# EnsembleSix.net
KiCad netlist of a schematic drawn in EAGLE
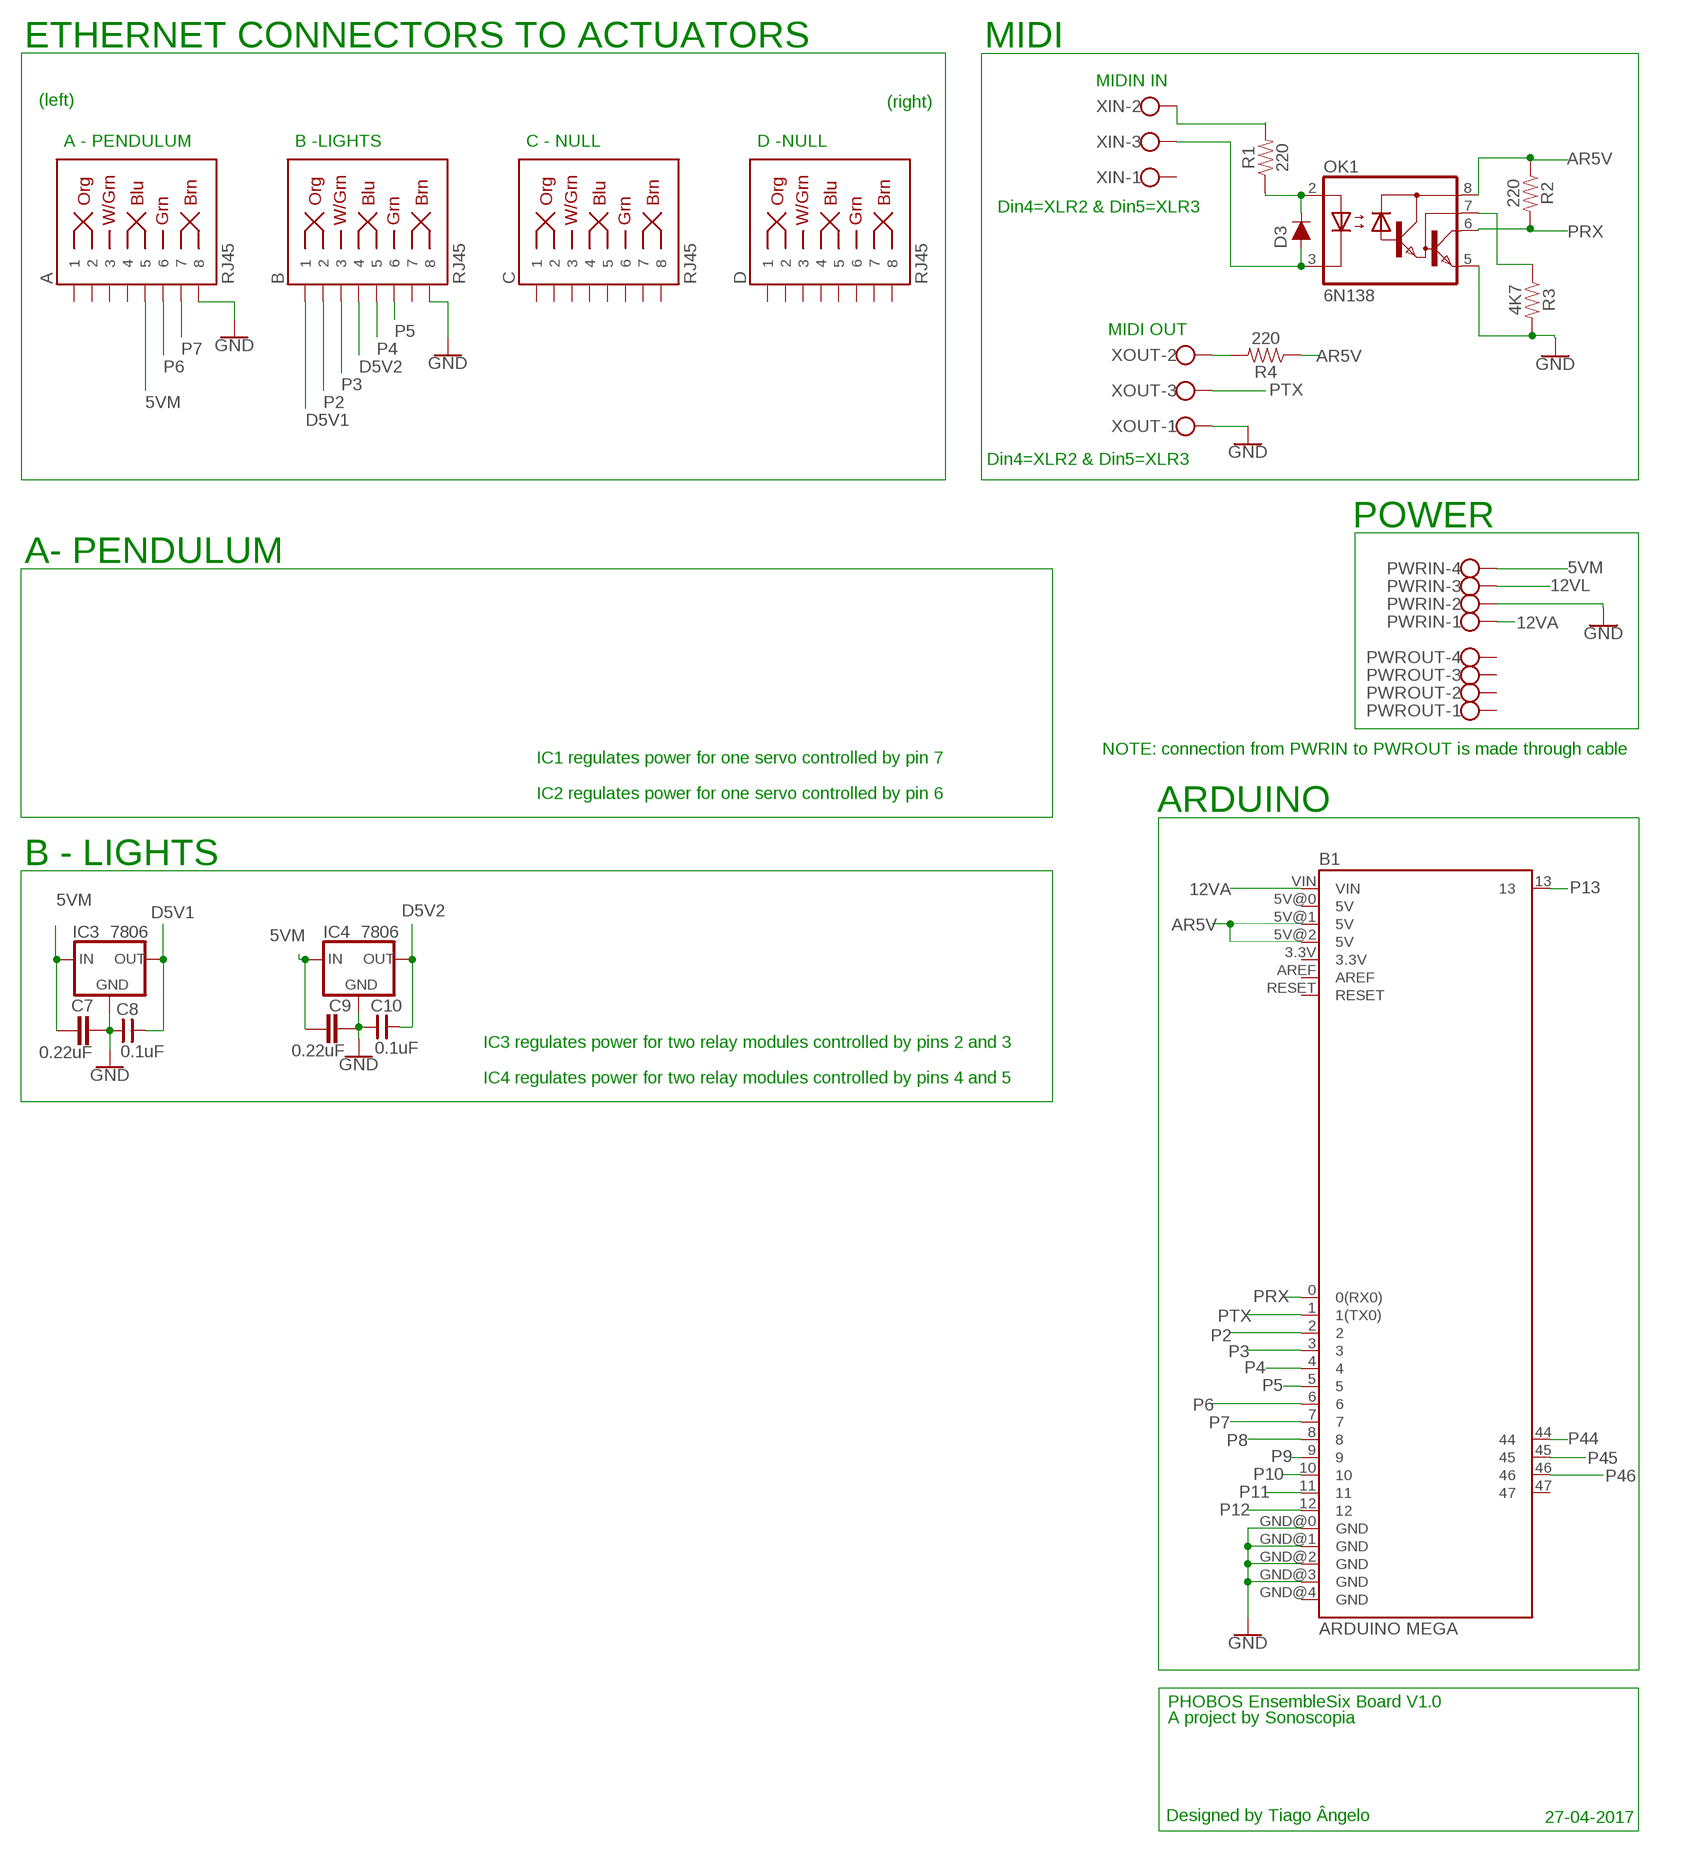
[diagram p0: schematic, sheet 1]

(export (version "E")
  (design (tool "Eeschema 10.0.6"))
  (components
    (comp (ref "A")
      (value "RJ45")
      (footprint "eagle-import:RJ45-8")
      (libsource (lib "eagle-import") (part "RJ45-8"))
    )
    (comp (ref "B")
      (value "RJ45")
      (footprint "eagle-import:RJ45-8")
      (libsource (lib "eagle-import") (part "RJ45-8"))
    )
    (comp (ref "B1")
      (value "ARDUINO MEGA")
      (footprint "eagle-import:ARDUINO_MEGA")
      (libsource (lib "eagle-import") (part "ARDUINO_MEGA_R3FULL"))
    )
    (comp (ref "C")
      (value "RJ45")
      (footprint "eagle-import:RJ45-8")
      (libsource (lib "eagle-import") (part "RJ45-8"))
    )
    (comp (ref "C7")
      (value "0.22uF")
      (footprint "eagle-import:C5B3")
      (libsource (lib "eagle-import") (part "C5/3"))
    )
    (comp (ref "C8")
      (value "0.1uF")
      (footprint "eagle-import:C025-050X025")
      (libsource (lib "eagle-import") (part "CNP-C025-050X025"))
    )
    (comp (ref "C9")
      (value "0.22uF")
      (footprint "eagle-import:C5B3")
      (libsource (lib "eagle-import") (part "C5/3"))
    )
    (comp (ref "C10")
      (value "0.1uF")
      (footprint "eagle-import:C025-050X025")
      (libsource (lib "eagle-import") (part "CNP-C025-050X025"))
    )
    (comp (ref "D")
      (value "RJ45")
      (footprint "eagle-import:RJ45-8")
      (libsource (lib "eagle-import") (part "RJ45-8"))
    )
    (comp (ref "D3")
      (value "200mA/100V/1V")
      (footprint "eagle-import:DIODE-1N4148")
      (libsource (lib "eagle-import") (part "DIODE-1N4148"))
    )
    (comp (ref "IC3")
      (value "7806")
      (footprint "eagle-import:78XXS")
      (libsource (lib "eagle-import") (part "78XXS"))
    )
    (comp (ref "IC4")
      (value "7806")
      (footprint "eagle-import:78XXS")
      (libsource (lib "eagle-import") (part "78XXS"))
    )
    (comp (ref "OK1")
      (value "6N138")
      (footprint "eagle-import:DIL08")
      (fields (field (name "MF") "VISHAY/TELEFUNKEN"))
      (libsource (lib "eagle-import") (part "6N138"))
    )
    (comp (ref "PWRIN")
      (value "W237-4")
      (footprint "eagle-import:W237-4")
      (libsource (lib "eagle-import") (part "W237-4"))
    )
    (comp (ref "PWROUT")
      (value "W237-4")
      (footprint "eagle-import:W237-4")
      (libsource (lib "eagle-import") (part "W237-4"))
    )
    (comp (ref "R1")
      (value "220")
      (footprint "eagle-import:AXIAL-0.3")
      (libsource (lib "eagle-import") (part "1KOHM-HORIZ-1/4W-5%"))
    )
    (comp (ref "R2")
      (value "220")
      (footprint "eagle-import:AXIAL-0.3")
      (libsource (lib "eagle-import") (part "1KOHM-HORIZ-1/4W-5%"))
    )
    (comp (ref "R3")
      (value "4K7")
      (footprint "eagle-import:AXIAL-0.3")
      (libsource (lib "eagle-import") (part "1KOHM-HORIZ-1/4W-5%"))
    )
    (comp (ref "R4")
      (value "220")
      (footprint "eagle-import:AXIAL-0.3")
      (libsource (lib "eagle-import") (part "1KOHM-HORIZ-1/4W-5%"))
    )
    (comp (ref "XIN")
      (value "W237-103")
      (footprint "eagle-import:W237-103")
      (fields (field (name "MPN") "237-103"))
      (libsource (lib "eagle-import") (part "W237-103"))
    )
    (comp (ref "XOUT")
      (value "W237-103")
      (footprint "eagle-import:W237-103")
      (fields (field (name "MPN") "237-103"))
      (libsource (lib "eagle-import") (part "W237-103"))
    )
  )
  (nets
    (net (code "1") (name "/5VM") (class "Default")
      (node (ref "A") (pin "5") (pinfunction "5_5") (pintype "bidirectional"))
      (node (ref "C7") (pin "1") (pinfunction "1_1") (pintype "passive"))
      (node (ref "C9") (pin "1") (pinfunction "1_1") (pintype "passive"))
      (node (ref "IC3") (pin "IN") (pinfunction "IN_IN") (pintype "input"))
      (node (ref "IC4") (pin "IN") (pinfunction "IN_IN") (pintype "input"))
      (node (ref "PWRIN") (pin "4") (pinfunction "KL_4") (pintype "passive"))
    )
    (net (code "2") (name "/12VA") (class "Default")
      (node (ref "B1") (pin "VIN") (pinfunction "VIN_VIN") (pintype "bidirectional"))
      (node (ref "PWRIN") (pin "1") (pinfunction "KL_1") (pintype "passive"))
    )
    (net (code "3") (name "/12VL") (class "Default")
      (node (ref "PWRIN") (pin "3") (pinfunction "KL_3") (pintype "passive"))
    )
    (net (code "4") (name "/AR5V") (class "Default")
      (node (ref "B1") (pin "5V@1") (pinfunction "5V_5V@1") (pintype "bidirectional"))
      (node (ref "B1") (pin "5V@2") (pinfunction "5V_5V@2") (pintype "bidirectional"))
      (node (ref "OK1") (pin "8") (pinfunction "VCC_8") (pintype "passive"))
      (node (ref "R2") (pin "P$1") (pinfunction "1_P$1") (pintype "passive"))
      (node (ref "R4") (pin "P$1") (pinfunction "1_P$1") (pintype "passive"))
    )
    (net (code "5") (name "/D5V1") (class "Default")
      (node (ref "B") (pin "1") (pinfunction "1_1") (pintype "bidirectional"))
      (node (ref "C8") (pin "2") (pinfunction "2_2") (pintype "passive"))
      (node (ref "IC3") (pin "OUT") (pinfunction "OUT_OUT") (pintype "passive"))
    )
    (net (code "6") (name "/D5V2") (class "Default")
      (node (ref "B") (pin "4") (pinfunction "4_4") (pintype "bidirectional"))
      (node (ref "C10") (pin "2") (pinfunction "2_2") (pintype "passive"))
      (node (ref "IC4") (pin "OUT") (pinfunction "OUT_OUT") (pintype "passive"))
    )
    (net (code "7") (name "/P2") (class "Default")
      (node (ref "B") (pin "2") (pinfunction "2_2") (pintype "bidirectional"))
      (node (ref "B1") (pin "2") (pinfunction "2_2") (pintype "bidirectional"))
    )
    (net (code "8") (name "/P3") (class "Default")
      (node (ref "B") (pin "3") (pinfunction "3_3") (pintype "bidirectional"))
      (node (ref "B1") (pin "3") (pinfunction "3_3") (pintype "bidirectional"))
    )
    (net (code "9") (name "/P4") (class "Default")
      (node (ref "B") (pin "5") (pinfunction "5_5") (pintype "bidirectional"))
      (node (ref "B1") (pin "4") (pinfunction "4_4") (pintype "bidirectional"))
    )
    (net (code "10") (name "/P5") (class "Default")
      (node (ref "B") (pin "6") (pinfunction "6_6") (pintype "bidirectional"))
      (node (ref "B1") (pin "5") (pinfunction "5_5") (pintype "bidirectional"))
    )
    (net (code "11") (name "/P6") (class "Default")
      (node (ref "A") (pin "6") (pinfunction "6_6") (pintype "bidirectional"))
      (node (ref "B1") (pin "6") (pinfunction "6_6") (pintype "bidirectional"))
    )
    (net (code "12") (name "/P7") (class "Default")
      (node (ref "A") (pin "7") (pinfunction "7_7") (pintype "bidirectional"))
      (node (ref "B1") (pin "7") (pinfunction "7_7") (pintype "bidirectional"))
    )
    (net (code "13") (name "/P8") (class "Default")
      (node (ref "B1") (pin "8") (pinfunction "8_8") (pintype "bidirectional"))
    )
    (net (code "14") (name "/P9") (class "Default")
      (node (ref "B1") (pin "9") (pinfunction "9_9") (pintype "bidirectional"))
    )
    (net (code "15") (name "/P10") (class "Default")
      (node (ref "B1") (pin "10") (pinfunction "10_10") (pintype "bidirectional"))
    )
    (net (code "16") (name "/P11") (class "Default")
      (node (ref "B1") (pin "11") (pinfunction "11_11") (pintype "bidirectional"))
    )
    (net (code "17") (name "/P12") (class "Default")
      (node (ref "B1") (pin "12") (pinfunction "12_12") (pintype "bidirectional"))
    )
    (net (code "18") (name "/P13") (class "Default")
      (node (ref "B1") (pin "13") (pinfunction "13_13") (pintype "bidirectional"))
    )
    (net (code "19") (name "/P44") (class "Default")
      (node (ref "B1") (pin "44") (pinfunction "44_44") (pintype "bidirectional"))
    )
    (net (code "20") (name "/P45") (class "Default")
      (node (ref "B1") (pin "45") (pinfunction "45_45") (pintype "bidirectional"))
    )
    (net (code "21") (name "/P46") (class "Default")
      (node (ref "B1") (pin "46") (pinfunction "46_46") (pintype "bidirectional"))
    )
    (net (code "22") (name "/PRX") (class "Default")
      (node (ref "B1") (pin "0") (pinfunction "0(RX0)_0") (pintype "bidirectional"))
      (node (ref "OK1") (pin "6") (pinfunction "VO_6") (pintype "passive"))
      (node (ref "R2") (pin "P$2") (pinfunction "2_P$2") (pintype "passive"))
    )
    (net (code "23") (name "/PTX") (class "Default")
      (node (ref "B1") (pin "1") (pinfunction "1(TX0)_1") (pintype "bidirectional"))
      (node (ref "XOUT") (pin "3") (pinfunction "KL_3") (pintype "passive"))
    )
    (net (code "24") (name "GND") (class "Default")
      (node (ref "A") (pin "8") (pinfunction "8_8") (pintype "bidirectional"))
      (node (ref "B") (pin "8") (pinfunction "8_8") (pintype "bidirectional"))
      (node (ref "B1") (pin "GND@0") (pinfunction "GND_GND@0") (pintype "bidirectional"))
      (node (ref "B1") (pin "GND@1") (pinfunction "GND_GND@1") (pintype "bidirectional"))
      (node (ref "B1") (pin "GND@2") (pinfunction "GND_GND@2") (pintype "bidirectional"))
      (node (ref "B1") (pin "GND@3") (pinfunction "GND_GND@3") (pintype "bidirectional"))
      (node (ref "C10") (pin "1") (pinfunction "1_1") (pintype "passive"))
      (node (ref "C7") (pin "2") (pinfunction "2_2") (pintype "passive"))
      (node (ref "C8") (pin "1") (pinfunction "1_1") (pintype "passive"))
      (node (ref "C9") (pin "2") (pinfunction "2_2") (pintype "passive"))
      (node (ref "IC3") (pin "GND") (pinfunction "GND_GND") (pintype "input"))
      (node (ref "IC4") (pin "GND") (pinfunction "GND_GND") (pintype "input"))
      (node (ref "OK1") (pin "5") (pinfunction "GND_5") (pintype "passive"))
      (node (ref "PWRIN") (pin "2") (pinfunction "KL_2") (pintype "passive"))
      (node (ref "R3") (pin "P$2") (pinfunction "2_P$2") (pintype "passive"))
      (node (ref "XOUT") (pin "1") (pinfunction "KL_1") (pintype "passive"))
    )
    (net (code "25") (name "Net-(OK1-A)") (class "Default")
      (node (ref "D3") (pin "C") (pinfunction "C_C") (pintype "passive"))
      (node (ref "OK1") (pin "2") (pinfunction "A_2") (pintype "passive"))
      (node (ref "R1") (pin "P$1") (pinfunction "1_P$1") (pintype "passive"))
    )
    (net (code "26") (name "Net-(OK1-C)") (class "Default")
      (node (ref "D3") (pin "A") (pinfunction "A_A") (pintype "passive"))
      (node (ref "OK1") (pin "3") (pinfunction "C_3") (pintype "passive"))
      (node (ref "XIN") (pin "3") (pinfunction "KL_3") (pintype "passive"))
    )
    (net (code "27") (name "Net-(OK1-VB)") (class "Default")
      (node (ref "OK1") (pin "7") (pinfunction "VB_7") (pintype "passive"))
      (node (ref "R3") (pin "P$1") (pinfunction "1_P$1") (pintype "passive"))
    )
    (net (code "28") (name "Net-(R1-2)") (class "Default")
      (node (ref "R1") (pin "P$2") (pinfunction "2_P$2") (pintype "passive"))
      (node (ref "XIN") (pin "2") (pinfunction "KL_2") (pintype "passive"))
    )
    (net (code "29") (name "Net-(R4-2)") (class "Default")
      (node (ref "R4") (pin "P$2") (pinfunction "2_P$2") (pintype "passive"))
      (node (ref "XOUT") (pin "2") (pinfunction "KL_2") (pintype "passive"))
    )
    (net (code "30") (name "unconnected-(A-Pad1)") (class "Default")
      (node (ref "A") (pin "1") (pinfunction "1_1") (pintype "bidirectional"))
    )
    (net (code "31") (name "unconnected-(A-Pad2)") (class "Default")
      (node (ref "A") (pin "2") (pinfunction "2_2") (pintype "bidirectional"))
    )
    (net (code "32") (name "unconnected-(A-Pad3)") (class "Default")
      (node (ref "A") (pin "3") (pinfunction "3_3") (pintype "bidirectional"))
    )
    (net (code "33") (name "unconnected-(A-Pad4)") (class "Default")
      (node (ref "A") (pin "4") (pinfunction "4_4") (pintype "bidirectional"))
    )
    (net (code "34") (name "unconnected-(B-Pad7)") (class "Default")
      (node (ref "B") (pin "7") (pinfunction "7_7") (pintype "bidirectional"))
    )
    (net (code "35") (name "unconnected-(B1-5V-Pad5V@0)") (class "Default")
      (node (ref "B1") (pin "5V@0") (pinfunction "5V_5V@0") (pintype "bidirectional"))
    )
    (net (code "36") (name "unconnected-(B1-GND-PadGND@4)") (class "Default")
      (node (ref "B1") (pin "GND@4") (pinfunction "GND_GND@4") (pintype "bidirectional"))
    )
    (net (code "37") (name "unconnected-(B1-Pad3.3V)") (class "Default")
      (node (ref "B1") (pin "3.3V") (pinfunction "3.3V_3.3V") (pintype "bidirectional"))
    )
    (net (code "38") (name "unconnected-(B1-Pad47)") (class "Default")
      (node (ref "B1") (pin "47") (pinfunction "47_47") (pintype "bidirectional"))
    )
    (net (code "39") (name "unconnected-(B1-PadAREF)") (class "Default")
      (node (ref "B1") (pin "AREF") (pinfunction "AREF_AREF") (pintype "bidirectional"))
    )
    (net (code "40") (name "unconnected-(B1-PadRESET)") (class "Default")
      (node (ref "B1") (pin "RESET") (pinfunction "RESET_RESET") (pintype "bidirectional"))
    )
    (net (code "41") (name "unconnected-(C-Pad1)") (class "Default")
      (node (ref "C") (pin "1") (pinfunction "1_1") (pintype "bidirectional"))
    )
    (net (code "42") (name "unconnected-(C-Pad2)") (class "Default")
      (node (ref "C") (pin "2") (pinfunction "2_2") (pintype "bidirectional"))
    )
    (net (code "43") (name "unconnected-(C-Pad3)") (class "Default")
      (node (ref "C") (pin "3") (pinfunction "3_3") (pintype "bidirectional"))
    )
    (net (code "44") (name "unconnected-(C-Pad4)") (class "Default")
      (node (ref "C") (pin "4") (pinfunction "4_4") (pintype "bidirectional"))
    )
    (net (code "45") (name "unconnected-(C-Pad5)") (class "Default")
      (node (ref "C") (pin "5") (pinfunction "5_5") (pintype "bidirectional"))
    )
    (net (code "46") (name "unconnected-(C-Pad6)") (class "Default")
      (node (ref "C") (pin "6") (pinfunction "6_6") (pintype "bidirectional"))
    )
    (net (code "47") (name "unconnected-(C-Pad7)") (class "Default")
      (node (ref "C") (pin "7") (pinfunction "7_7") (pintype "bidirectional"))
    )
    (net (code "48") (name "unconnected-(C-Pad8)") (class "Default")
      (node (ref "C") (pin "8") (pinfunction "8_8") (pintype "bidirectional"))
    )
    (net (code "49") (name "unconnected-(D-Pad1)") (class "Default")
      (node (ref "D") (pin "1") (pinfunction "1_1") (pintype "bidirectional"))
    )
    (net (code "50") (name "unconnected-(D-Pad2)") (class "Default")
      (node (ref "D") (pin "2") (pinfunction "2_2") (pintype "bidirectional"))
    )
    (net (code "51") (name "unconnected-(D-Pad3)") (class "Default")
      (node (ref "D") (pin "3") (pinfunction "3_3") (pintype "bidirectional"))
    )
    (net (code "52") (name "unconnected-(D-Pad4)") (class "Default")
      (node (ref "D") (pin "4") (pinfunction "4_4") (pintype "bidirectional"))
    )
    (net (code "53") (name "unconnected-(D-Pad5)") (class "Default")
      (node (ref "D") (pin "5") (pinfunction "5_5") (pintype "bidirectional"))
    )
    (net (code "54") (name "unconnected-(D-Pad6)") (class "Default")
      (node (ref "D") (pin "6") (pinfunction "6_6") (pintype "bidirectional"))
    )
    (net (code "55") (name "unconnected-(D-Pad7)") (class "Default")
      (node (ref "D") (pin "7") (pinfunction "7_7") (pintype "bidirectional"))
    )
    (net (code "56") (name "unconnected-(D-Pad8)") (class "Default")
      (node (ref "D") (pin "8") (pinfunction "8_8") (pintype "bidirectional"))
    )
    (net (code "57") (name "unconnected-(PWROUTA-KL-Pad1)") (class "Default")
      (node (ref "PWROUT") (pin "1") (pinfunction "KL_1") (pintype "passive"))
    )
    (net (code "58") (name "unconnected-(PWROUTB-KL-Pad2)") (class "Default")
      (node (ref "PWROUT") (pin "2") (pinfunction "KL_2") (pintype "passive"))
    )
    (net (code "59") (name "unconnected-(PWROUTC-KL-Pad3)") (class "Default")
      (node (ref "PWROUT") (pin "3") (pinfunction "KL_3") (pintype "passive"))
    )
    (net (code "60") (name "unconnected-(PWROUTD-KL-Pad4)") (class "Default")
      (node (ref "PWROUT") (pin "4") (pinfunction "KL_4") (pintype "passive"))
    )
    (net (code "61") (name "unconnected-(XINA-KL-Pad1)") (class "Default")
      (node (ref "XIN") (pin "1") (pinfunction "KL_1") (pintype "passive"))
    )
  )
)
